# PainRegister_Bridge.net
KiCad netlist of a schematic drawn in Altium Designer
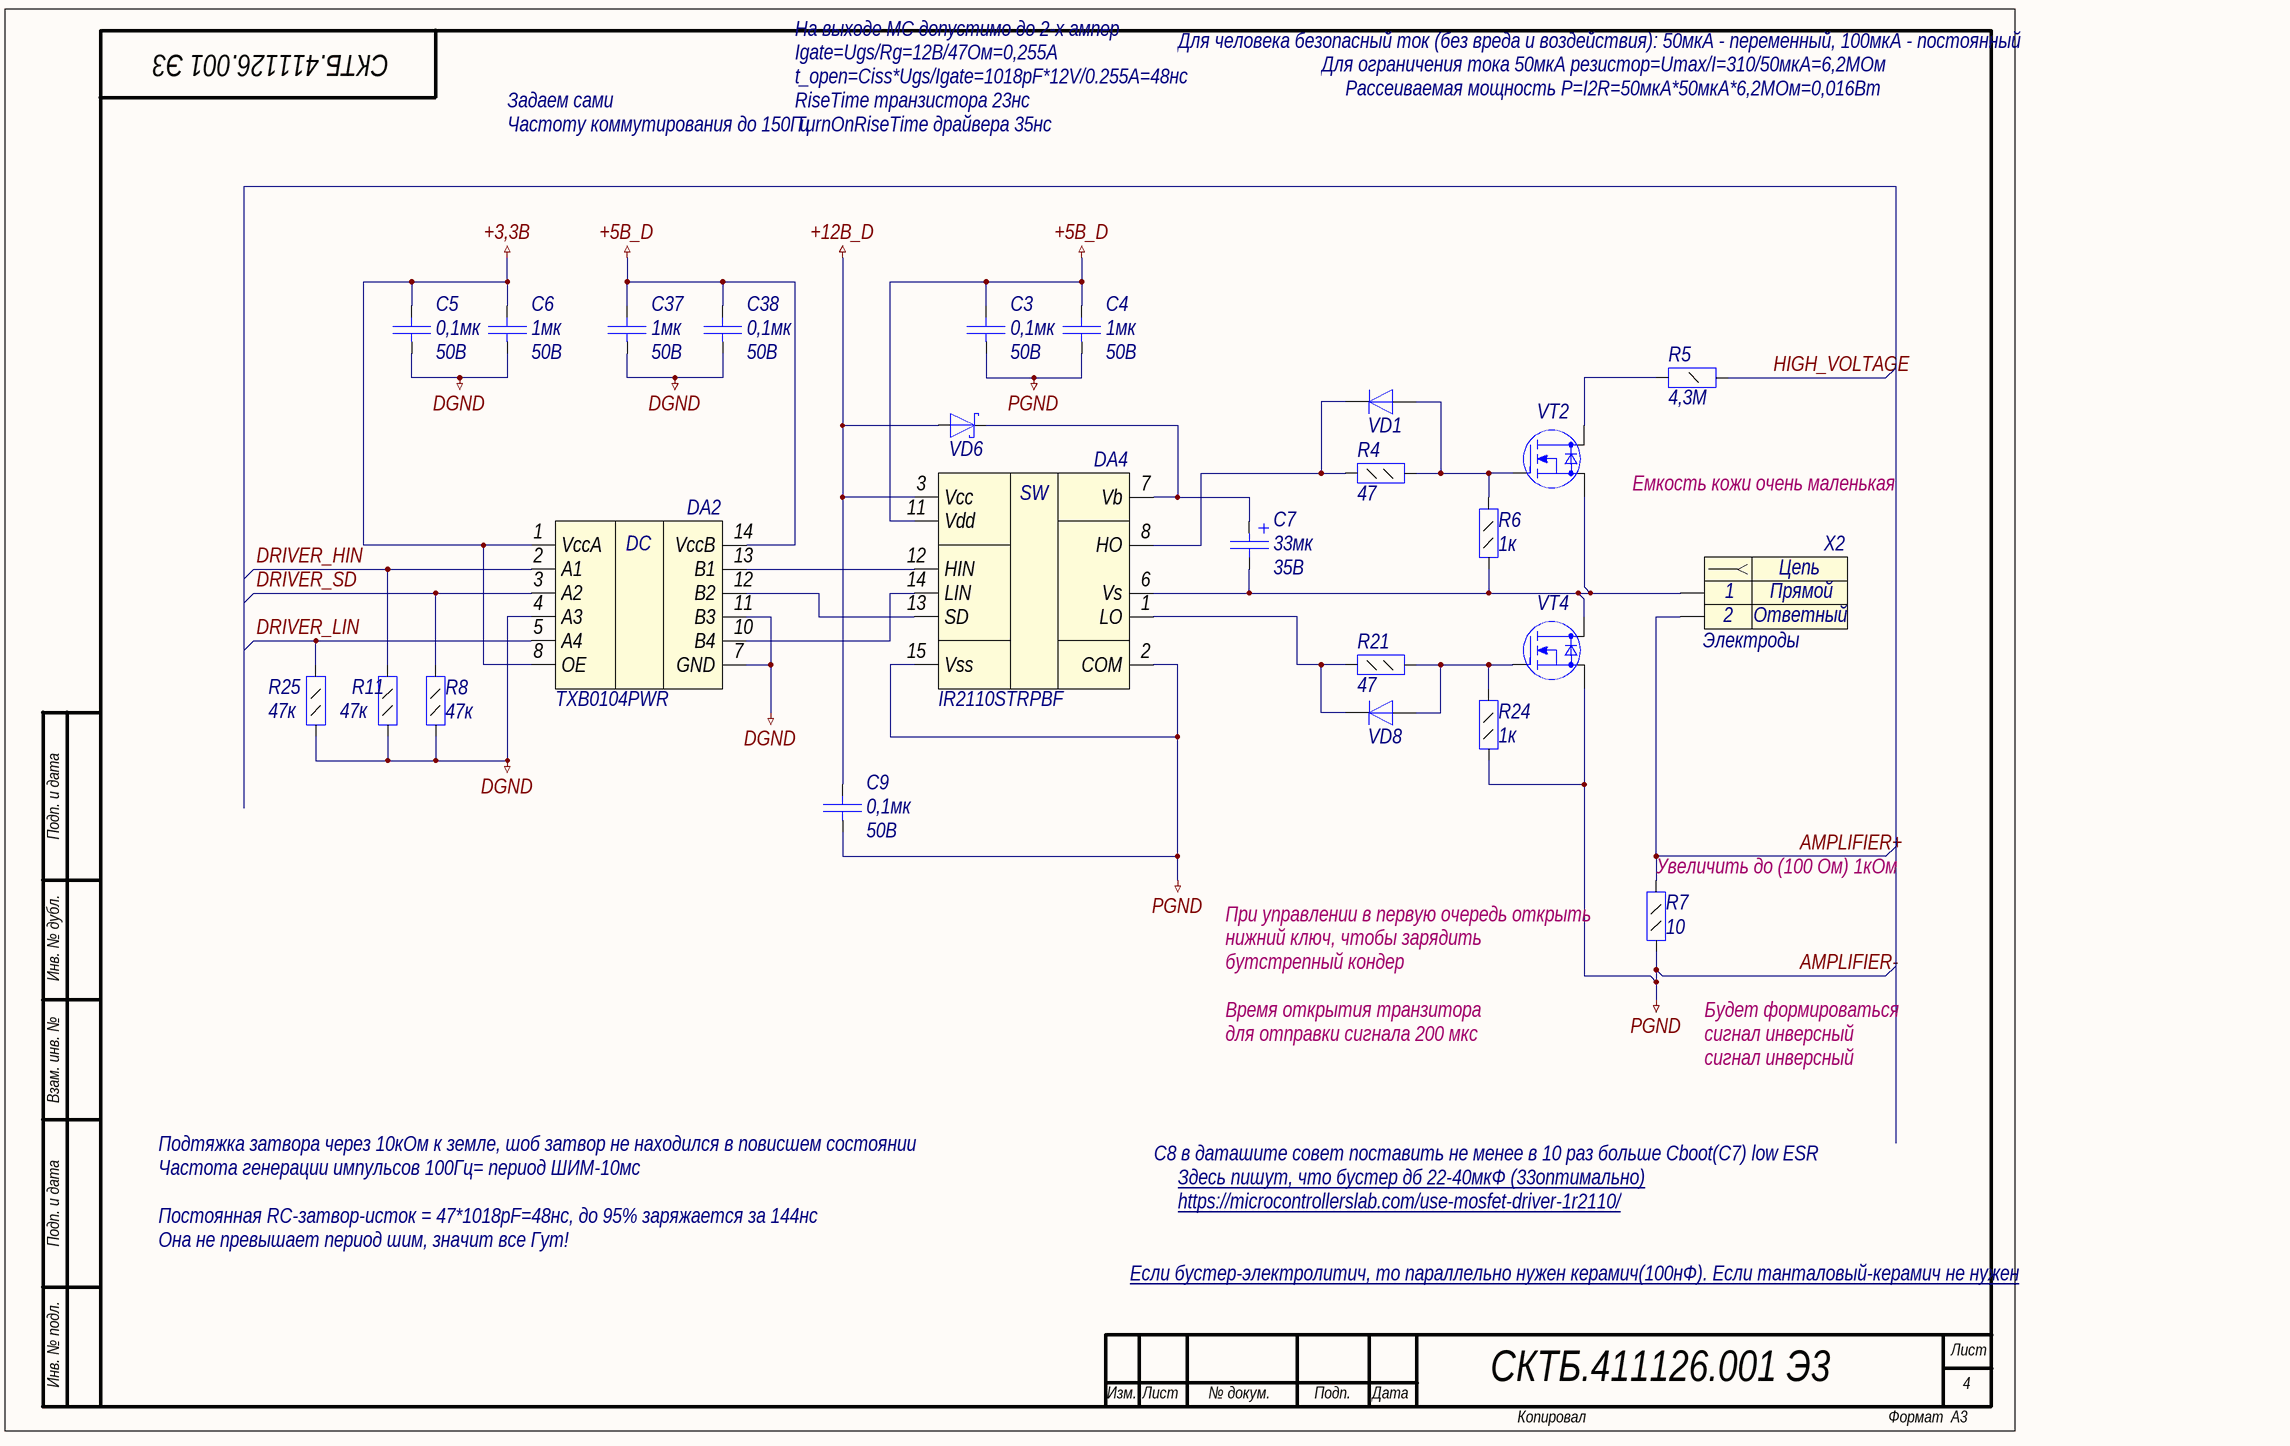
[diagram p0: PainRegister_Bridge.SchDoc]

(export (version "E")
  (design (tool "Eeschema 10.0.6"))
  (components
    (comp (ref "C3")
      (value "0,1мк")
      (footprint "C0805")
      (description "Конденсатор")
      (fields
        (field (name "VOLTAGE") "50В")
        (field (name "PART NUMBER") "GRM21BR71H104KA01L ")
        (field (name "Comment") "Capacitor")
      )
      (libsource (lib "MOP44") (part "Capacitor"))
    )
    (comp (ref "C4")
      (value "1мк")
      (footprint "C0805")
      (description "Конденсатор")
      (fields
        (field (name "VOLTAGE") "50B")
        (field (name "PART NUMBER") "GRM21BR71H105K")
        (field (name "Comment") "Capacitor")
      )
      (libsource (lib "MOP44") (part "Capacitor"))
    )
    (comp (ref "C5")
      (value "0,1мк")
      (footprint "C0805")
      (description "Конденсатор")
      (fields
        (field (name "VOLTAGE") "50В")
        (field (name "PART NUMBER") "GRM21BR71H104KA01L ")
        (field (name "Comment") "Capacitor")
      )
      (libsource (lib "MOP44") (part "Capacitor"))
    )
    (comp (ref "C6")
      (value "1мк")
      (footprint "C0805")
      (description "Конденсатор")
      (fields
        (field (name "VOLTAGE") "50B")
        (field (name "PART NUMBER") "GRM21BR71H105K")
        (field (name "Comment") "Capacitor")
      )
      (libsource (lib "MOP44") (part "Capacitor"))
    )
    (comp (ref "C7")
      (value "33мк")
      (footprint "TANTAL CASE D")
      (description "Конденсатор полярный")
      (fields
        (field (name "VOLTAGE") "35В")
        (field (name "PART NUMBER") "TAJD336K035RNJ")
        (field (name "Comment") "Capacitor_pol")
      )
      (libsource (lib "MOP44") (part "Capacitor_pol"))
    )
    (comp (ref "C9")
      (value "0,1мк")
      (footprint "C0805")
      (description "Конденсатор")
      (fields
        (field (name "VOLTAGE") "50В")
        (field (name "PART NUMBER") "GRM21BR71H104KA01L ")
        (field (name "Comment") "Capacitor")
      )
      (libsource (lib "MOP44") (part "Capacitor"))
    )
    (comp (ref "C37")
      (value "1мк")
      (footprint "C0805")
      (description "Конденсатор")
      (fields
        (field (name "VOLTAGE") "50B")
        (field (name "PART NUMBER") "GRM21BR71H105K")
        (field (name "Comment") "Capacitor")
      )
      (libsource (lib "MOP44") (part "Capacitor"))
    )
    (comp (ref "C38")
      (value "0,1мк")
      (footprint "C0805")
      (description "Конденсатор")
      (fields
        (field (name "VOLTAGE") "50В")
        (field (name "PART NUMBER") "GRM21BR71H104KA01L ")
        (field (name "Comment") "Capacitor")
      )
      (libsource (lib "MOP44") (part "Capacitor"))
    )
    (comp (ref "DA2")
      (value "TXB0104")
      (footprint "TSSOP14")
      (description "4-Bit Bidirectional Voltage-level Translator")
      (fields (field (name "PART NUMBER") "TXB0104PWR") (field (name "MANUFACTURER") "Texas Instruments"))
      (libsource (lib "MOP44") (part "TXB0104"))
    )
    (comp (ref "DA4")
      (value "IR2110S")
      (footprint "SO16")
      (description "High and Low Side Driver")
      (fields (field (name "PART NUMBER") "IR2110STRPBF"))
      (libsource (lib "MOP44") (part "IR2110S"))
    )
    (comp (ref "R4")
      (value "47")
      (footprint "R0805")
      (description "Резистор")
      (fields (field (name "PART NUMBER") "RC0805FR-0747RL") (field (name "POWER") "0,125Вт"))
      (libsource (lib "") (part "Resistor_0,125Вт_1"))
    )
    (comp (ref "R5")
      (value "4,3М")
      (footprint "R1206")
      (description "Резистор")
      (fields (field (name "PART NUMBER") "RC1206FR-074M3") (field (name "POWER") "0,25Вт"))
      (libsource (lib "MOP44") (part "Resistor_0,25Вт"))
    )
    (comp (ref "R6")
      (value "1к")
      (footprint "R0805")
      (description "Резистор")
      (fields (field (name "PART NUMBER") "RC0805FR-071KL") (field (name "POWER") "0,125Вт"))
      (libsource (lib "MOP44") (part "Resistor_0,125Вт"))
    )
    (comp (ref "R7")
      (value "10")
      (footprint "R0805")
      (description "Резистор")
      (fields (field (name "PART NUMBER") "RC0805FR-0710RL") (field (name "POWER") "0,125Вт"))
      (libsource (lib "MOP44") (part "Resistor_0,125Вт"))
    )
    (comp (ref "R8")
      (value "47к")
      (footprint "R0805")
      (description "Резистор")
      (fields (field (name "PART NUMBER") "RC0805FR-0747KL") (field (name "POWER") "0,125Вт"))
      (libsource (lib "MOP44") (part "Resistor_0,125Вт"))
    )
    (comp (ref "R11")
      (value "47к")
      (footprint "R0805")
      (description "Резистор")
      (fields (field (name "PART NUMBER") "RC0805FR-0747KL") (field (name "POWER") "0,125Вт"))
      (libsource (lib "MOP44") (part "Resistor_0,125Вт"))
    )
    (comp (ref "R21")
      (value "47")
      (footprint "R0805")
      (description "Резистор")
      (fields (field (name "PART NUMBER") "RC0805FR-0747RL") (field (name "POWER") "0,125Вт"))
      (libsource (lib "") (part "Resistor_0,125Вт_1"))
    )
    (comp (ref "R24")
      (value "1к")
      (footprint "R0805")
      (description "Резистор")
      (fields (field (name "PART NUMBER") "RC0805FR-071KL") (field (name "POWER") "0,125Вт"))
      (libsource (lib "MOP44") (part "Resistor_0,125Вт"))
    )
    (comp (ref "R25")
      (value "47к")
      (footprint "R0805")
      (description "Резистор")
      (fields (field (name "PART NUMBER") "RC0805FR-0747KL") (field (name "POWER") "0,125Вт"))
      (libsource (lib "MOP44") (part "Resistor_0,125Вт"))
    )
    (comp (ref "VD1")
      (value "Diode")
      (footprint "SMA")
      (description "Диод")
      (fields (field (name "PART NUMBER") "SMA4007"))
      (libsource (lib "MOP44") (part "Diode"))
    )
    (comp (ref "VD6")
      (value "DiodeSchottky")
      (footprint "SMA")
      (description "Диод Шоттки")
      (fields (field (name "PART NUMBER") "SK34A"))
      (libsource (lib "MOP44") (part "DiodeSchottky"))
    )
    (comp (ref "VD8")
      (value "Diode")
      (footprint "SMA")
      (description "Диод")
      (fields (field (name "PART NUMBER") "SMA4007"))
      (libsource (lib "MOP44") (part "Diode"))
    )
    (comp (ref "VT2")
      (value "N-MOSFET")
      (footprint "D2PAK")
      (fields (field (name "PART NUMBER") "IRF840ASPBF") (field (name "MANUFACTURER") "Vishay"))
      (libsource (lib "MOP44") (part "N-MOSFET"))
    )
    (comp (ref "VT4")
      (value "N-MOSFET")
      (footprint "D2PAK")
      (fields (field (name "PART NUMBER") "IRF840ASPBF") (field (name "MANUFACTURER") "Vishay"))
      (libsource (lib "MOP44") (part "N-MOSFET"))
    )
    (comp (ref "X2")
      (value "Электроды")
      (footprint "CWF-2R")
      (description "Разъем - 2 конт. розетка")
      (fields (field (name "PART NUMBER") "DS1069-2 MR-A"))
      (libsource (lib "MOP44") (part "Header_2_sct"))
    )
  )
  (nets
    (net (code "1") (name "+3,3В") (class "Default")
      (node (ref "C5") (pin "2") (pinfunction "2_2") (pintype "passive"))
      (node (ref "C6") (pin "2") (pinfunction "2_2") (pintype "passive"))
      (node (ref "DA2") (pin "1") (pinfunction "VccA_1") (pintype "power_in"))
      (node (ref "DA2") (pin "8") (pinfunction "OE_8") (pintype "power_in"))
    )
    (net (code "2") (name "+5B_D") (class "Default")
      (node (ref "C3") (pin "2") (pinfunction "2_2") (pintype "passive"))
      (node (ref "C37") (pin "2") (pinfunction "2_2") (pintype "passive"))
      (node (ref "C38") (pin "2") (pinfunction "2_2") (pintype "passive"))
      (node (ref "C4") (pin "2") (pinfunction "2_2") (pintype "passive"))
      (node (ref "DA2") (pin "14") (pinfunction "VccB_14") (pintype "power_in"))
      (node (ref "DA4") (pin "11") (pinfunction "Vdd_11") (pintype "passive"))
    )
    (net (code "3") (name "+12В_D") (class "Default")
      (node (ref "C9") (pin "2") (pinfunction "2_2") (pintype "passive"))
      (node (ref "DA4") (pin "3") (pinfunction "Vcc_3") (pintype "passive"))
      (node (ref "VD6") (pin "2") (pinfunction "A_2") (pintype "passive"))
    )
    (net (code "4") (name "/AMPLIFIER+") (class "Default")
      (node (ref "R7") (pin "2") (pinfunction "2_2") (pintype "passive"))
      (node (ref "X2") (pin "2") (pinfunction "2_2") (pintype "passive"))
    )
    (net (code "5") (name "/DRIVER_HIN") (class "Default")
      (node (ref "DA2") (pin "2") (pinfunction "A1_2") (pintype "power_in"))
      (node (ref "R11") (pin "2") (pinfunction "2_2") (pintype "passive"))
    )
    (net (code "6") (name "/DRIVER_LIN") (class "Default")
      (node (ref "DA2") (pin "5") (pinfunction "A4_5") (pintype "power_in"))
      (node (ref "R25") (pin "2") (pinfunction "2_2") (pintype "passive"))
    )
    (net (code "7") (name "/DRIVER_SD") (class "Default")
      (node (ref "DA2") (pin "3") (pinfunction "A2_3") (pintype "power_in"))
      (node (ref "R8") (pin "2") (pinfunction "2_2") (pintype "passive"))
    )
    (net (code "8") (name "/HIGH_VOLTAGE") (class "Default")
      (node (ref "R5") (pin "2") (pinfunction "2_2") (pintype "passive"))
    )
    (net (code "9") (name "DGND") (class "Default")
      (node (ref "C37") (pin "1") (pinfunction "1_1") (pintype "passive"))
      (node (ref "C38") (pin "1") (pinfunction "1_1") (pintype "passive"))
      (node (ref "C5") (pin "1") (pinfunction "1_1") (pintype "passive"))
      (node (ref "C6") (pin "1") (pinfunction "1_1") (pintype "passive"))
      (node (ref "DA2") (pin "11") (pinfunction "B3_11") (pintype "power_in"))
      (node (ref "DA2") (pin "4") (pinfunction "A3_4") (pintype "power_in"))
      (node (ref "DA2") (pin "7") (pinfunction "GND_7") (pintype "power_in"))
      (node (ref "R11") (pin "1") (pinfunction "1_1") (pintype "passive"))
      (node (ref "R25") (pin "1") (pinfunction "1_1") (pintype "passive"))
      (node (ref "R8") (pin "1") (pinfunction "1_1") (pintype "passive"))
    )
    (net (code "10") (name "Net-(DA2-B1)") (class "Default")
      (node (ref "DA2") (pin "13") (pinfunction "B1_13") (pintype "power_in"))
      (node (ref "DA4") (pin "12") (pinfunction "HIN_12") (pintype "passive"))
    )
    (net (code "11") (name "Net-(DA2-B2)") (class "Default")
      (node (ref "DA2") (pin "12") (pinfunction "B2_12") (pintype "power_in"))
      (node (ref "DA4") (pin "13") (pinfunction "SD_13") (pintype "passive"))
    )
    (net (code "12") (name "Net-(DA2-B4)") (class "Default")
      (node (ref "DA2") (pin "10") (pinfunction "B4_10") (pintype "power_in"))
      (node (ref "DA4") (pin "14") (pinfunction "LIN_14") (pintype "passive"))
    )
    (net (code "13") (name "Net-(DA4-HO)") (class "Default")
      (node (ref "DA4") (pin "8") (pinfunction "HO_8") (pintype "passive"))
      (node (ref "R4") (pin "1") (pinfunction "1_1") (pintype "passive"))
      (node (ref "VD1") (pin "1") (pinfunction "K_1") (pintype "passive"))
    )
    (net (code "14") (name "Net-(DA4-LO)") (class "Default")
      (node (ref "DA4") (pin "1") (pinfunction "LO_1") (pintype "passive"))
      (node (ref "R21") (pin "1") (pinfunction "1_1") (pintype "passive"))
      (node (ref "VD8") (pin "1") (pinfunction "K_1") (pintype "passive"))
    )
    (net (code "15") (name "Net-(DA4-Vb)") (class "Default")
      (node (ref "C7") (pin "1") (pinfunction "1_1") (pintype "passive"))
      (node (ref "DA4") (pin "7") (pinfunction "Vb_7") (pintype "passive"))
      (node (ref "VD6") (pin "1") (pinfunction "K_1") (pintype "passive"))
    )
    (net (code "16") (name "Net-(DA4-Vs)") (class "Default")
      (node (ref "C7") (pin "2") (pinfunction "2_2") (pintype "passive"))
      (node (ref "DA4") (pin "6") (pinfunction "Vs_6") (pintype "passive"))
      (node (ref "R6") (pin "1") (pinfunction "1_1") (pintype "passive"))
      (node (ref "VT2") (pin "3") (pinfunction "S_3") (pintype "passive"))
      (node (ref "VT4") (pin "2") (pinfunction "D_2") (pintype "passive"))
      (node (ref "X2") (pin "1") (pinfunction "1_1") (pintype "passive"))
    )
    (net (code "17") (name "Net-(VD1-A)") (class "Default")
      (node (ref "R4") (pin "2") (pinfunction "2_2") (pintype "passive"))
      (node (ref "R6") (pin "2") (pinfunction "2_2") (pintype "passive"))
      (node (ref "VD1") (pin "2") (pinfunction "A_2") (pintype "passive"))
      (node (ref "VT2") (pin "1") (pinfunction "G_1") (pintype "passive"))
    )
    (net (code "18") (name "Net-(VD8-A)") (class "Default")
      (node (ref "R21") (pin "2") (pinfunction "2_2") (pintype "passive"))
      (node (ref "R24") (pin "2") (pinfunction "2_2") (pintype "passive"))
      (node (ref "VD8") (pin "2") (pinfunction "A_2") (pintype "passive"))
      (node (ref "VT4") (pin "1") (pinfunction "G_1") (pintype "passive"))
    )
    (net (code "19") (name "Net-(VT2-D)") (class "Default")
      (node (ref "R5") (pin "1") (pinfunction "1_1") (pintype "passive"))
      (node (ref "VT2") (pin "2") (pinfunction "D_2") (pintype "passive"))
    )
    (net (code "20") (name "PGND") (class "Default")
      (node (ref "C3") (pin "1") (pinfunction "1_1") (pintype "passive"))
      (node (ref "C4") (pin "1") (pinfunction "1_1") (pintype "passive"))
      (node (ref "C9") (pin "1") (pinfunction "1_1") (pintype "passive"))
      (node (ref "DA4") (pin "15") (pinfunction "Vss_15") (pintype "passive"))
      (node (ref "DA4") (pin "2") (pinfunction "COM_2") (pintype "passive"))
      (node (ref "R24") (pin "1") (pinfunction "1_1") (pintype "passive"))
      (node (ref "R7") (pin "1") (pinfunction "1_1") (pintype "passive"))
      (node (ref "VT4") (pin "3") (pinfunction "S_3") (pintype "passive"))
    )
  )
)
